# zero-hm-10-breakout.net
KiCad netlist of a schematic drawn in EAGLE
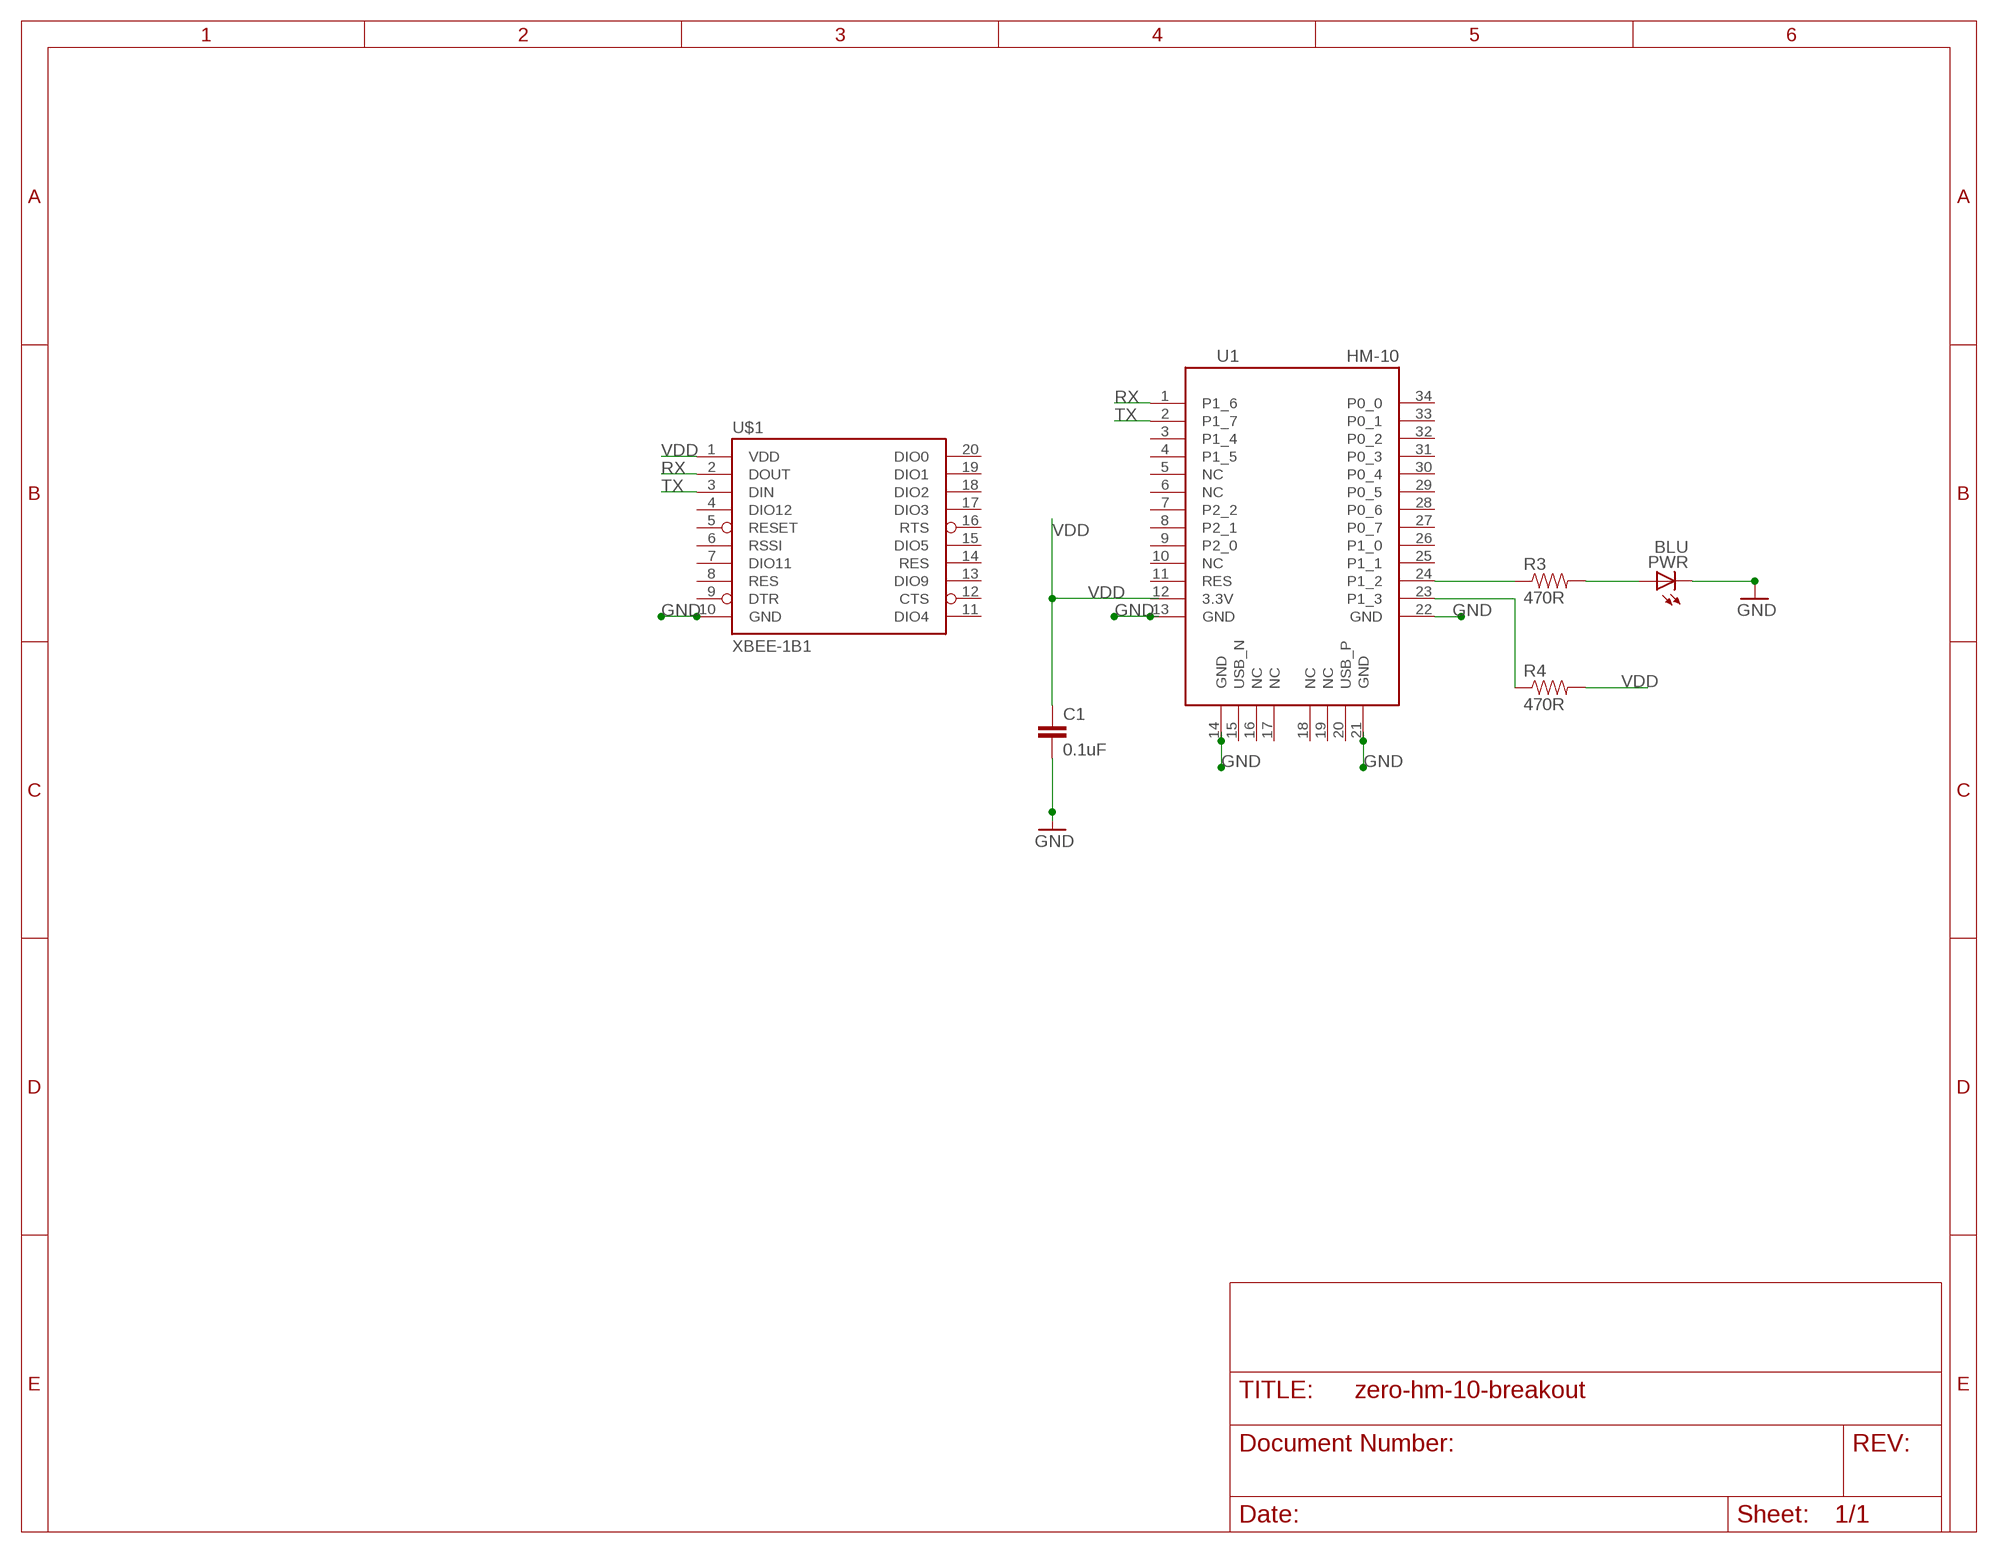
[diagram p0: schematic, sheet 1]

(export (version "E")
  (design (tool "Eeschema 10.0.6"))
  (components
    (comp (ref "C1")
      (value "0.1uF")
      (footprint "eagle-import:0603-CAP")
      (libsource (lib "eagle-import") (part "0.1UF-25V(+80/-20%)(0603)"))
    )
    (comp (ref "PWR")
      (value "BLU")
      (footprint "eagle-import:CHIPLED_0805")
      (libsource (lib "eagle-import") (part "LEDCHIPLED_0805"))
    )
    (comp (ref "R3")
      (value "470R")
      (footprint "eagle-import:0805")
      (libsource (lib "eagle-import") (part "0.3OHM-1/8W-1%(0805)"))
    )
    (comp (ref "R4")
      (value "470R")
      (footprint "eagle-import:0805")
      (libsource (lib "eagle-import") (part "0.3OHM-1/8W-1%(0805)"))
    )
    (comp (ref "U$1")
      (value "XBEE-1B1")
      (footprint "eagle-import:XBEE-1")
      (libsource (lib "eagle-import") (part "XBEE-1B1"))
    )
    (comp (ref "U1")
      (value "HM-10")
      (footprint "eagle-import:HM-10")
      (libsource (lib "eagle-import") (part "HM-10"))
    )
  )
  (nets
    (net (code "1") (name "/RX") (class "Default")
      (node (ref "U$1") (pin "2") (pinfunction "DOUT_2") (pintype "output"))
      (node (ref "U1") (pin "1") (pinfunction "P1_6_1") (pintype "bidirectional"))
    )
    (net (code "2") (name "/TX") (class "Default")
      (node (ref "U$1") (pin "3") (pinfunction "DIN_3") (pintype "input"))
      (node (ref "U1") (pin "2") (pinfunction "P1_7_2") (pintype "bidirectional"))
    )
    (net (code "3") (name "/VDD") (class "Default")
      (node (ref "C1") (pin "1") (pinfunction "1_1") (pintype "passive"))
      (node (ref "R4") (pin "2") (pinfunction "2_2") (pintype "passive"))
      (node (ref "U$1") (pin "1") (pinfunction "VDD_1") (pintype "power_in"))
      (node (ref "U1") (pin "12") (pinfunction "3.3V_12") (pintype "bidirectional"))
    )
    (net (code "4") (name "GND") (class "Default")
      (node (ref "C1") (pin "2") (pinfunction "2_2") (pintype "passive"))
      (node (ref "PWR") (pin "C") (pinfunction "C_C") (pintype "passive"))
      (node (ref "U$1") (pin "10") (pinfunction "GND_10") (pintype "power_in"))
      (node (ref "U1") (pin "13") (pinfunction "GND_13") (pintype "bidirectional"))
      (node (ref "U1") (pin "14") (pinfunction "GND_14") (pintype "bidirectional"))
      (node (ref "U1") (pin "21") (pinfunction "GND_21") (pintype "bidirectional"))
      (node (ref "U1") (pin "22") (pinfunction "GND_22") (pintype "bidirectional"))
    )
    (net (code "5") (name "Net-(PWR-PadA)") (class "Default")
      (node (ref "PWR") (pin "A") (pinfunction "A_A") (pintype "passive"))
      (node (ref "R3") (pin "2") (pinfunction "2_2") (pintype "passive"))
    )
    (net (code "6") (name "Net-(U1-P1_2)") (class "Default")
      (node (ref "R3") (pin "1") (pinfunction "1_1") (pintype "passive"))
      (node (ref "U1") (pin "24") (pinfunction "P1_2_24") (pintype "bidirectional"))
    )
    (net (code "7") (name "Net-(U1-P1_3)") (class "Default")
      (node (ref "R4") (pin "1") (pinfunction "1_1") (pintype "passive"))
      (node (ref "U1") (pin "23") (pinfunction "P1_3_23") (pintype "bidirectional"))
    )
    (net (code "8") (name "unconnected-(U$1-CTS-Pad12)") (class "Default")
      (node (ref "U$1") (pin "12") (pinfunction "CTS_12") (pintype "output"))
    )
    (net (code "9") (name "unconnected-(U$1-DIO0-Pad20)") (class "Default")
      (node (ref "U$1") (pin "20") (pinfunction "DIO0_20") (pintype "bidirectional"))
    )
    (net (code "10") (name "unconnected-(U$1-DIO1-Pad19)") (class "Default")
      (node (ref "U$1") (pin "19") (pinfunction "DIO1_19") (pintype "bidirectional"))
    )
    (net (code "11") (name "unconnected-(U$1-DIO2-Pad18)") (class "Default")
      (node (ref "U$1") (pin "18") (pinfunction "DIO2_18") (pintype "bidirectional"))
    )
    (net (code "12") (name "unconnected-(U$1-DIO3-Pad17)") (class "Default")
      (node (ref "U$1") (pin "17") (pinfunction "DIO3_17") (pintype "bidirectional"))
    )
    (net (code "13") (name "unconnected-(U$1-DIO4-Pad11)") (class "Default")
      (node (ref "U$1") (pin "11") (pinfunction "DIO4_11") (pintype "bidirectional"))
    )
    (net (code "14") (name "unconnected-(U$1-DIO5-Pad15)") (class "Default")
      (node (ref "U$1") (pin "15") (pinfunction "DIO5_15") (pintype "bidirectional"))
    )
    (net (code "15") (name "unconnected-(U$1-DIO9-Pad13)") (class "Default")
      (node (ref "U$1") (pin "13") (pinfunction "DIO9_13") (pintype "bidirectional"))
    )
    (net (code "16") (name "unconnected-(U$1-DIO11-Pad7)") (class "Default")
      (node (ref "U$1") (pin "7") (pinfunction "DIO11_7") (pintype "bidirectional"))
    )
    (net (code "17") (name "unconnected-(U$1-DIO12-Pad4)") (class "Default")
      (node (ref "U$1") (pin "4") (pinfunction "DIO12_4") (pintype "bidirectional"))
    )
    (net (code "18") (name "unconnected-(U$1-DTR-Pad9)") (class "Default")
      (node (ref "U$1") (pin "9") (pinfunction "DTR_9") (pintype "bidirectional"))
    )
    (net (code "19") (name "unconnected-(U$1-RES-Pad8)") (class "Default")
      (node (ref "U$1") (pin "8") (pinfunction "RES_8") (pintype "bidirectional"))
    )
    (net (code "20") (name "unconnected-(U$1-RES-Pad14)") (class "Default")
      (node (ref "U$1") (pin "14") (pinfunction "RES_14") (pintype "bidirectional"))
    )
    (net (code "21") (name "unconnected-(U$1-RESET-Pad5)") (class "Default")
      (node (ref "U$1") (pin "5") (pinfunction "RESET_5") (pintype "input"))
    )
    (net (code "22") (name "unconnected-(U$1-RSSI-Pad6)") (class "Default")
      (node (ref "U$1") (pin "6") (pinfunction "RSSI_6") (pintype "bidirectional"))
    )
    (net (code "23") (name "unconnected-(U$1-RTS-Pad16)") (class "Default")
      (node (ref "U$1") (pin "16") (pinfunction "RTS_16") (pintype "input"))
    )
    (net (code "24") (name "unconnected-(U1-NC-Pad5)") (class "Default")
      (node (ref "U1") (pin "5") (pinfunction "NC_5") (pintype "bidirectional"))
    )
    (net (code "25") (name "unconnected-(U1-NC-Pad6)") (class "Default")
      (node (ref "U1") (pin "6") (pinfunction "NC_6") (pintype "bidirectional"))
    )
    (net (code "26") (name "unconnected-(U1-NC-Pad10)") (class "Default")
      (node (ref "U1") (pin "10") (pinfunction "NC_10") (pintype "bidirectional"))
    )
    (net (code "27") (name "unconnected-(U1-NC-Pad16)") (class "Default")
      (node (ref "U1") (pin "16") (pinfunction "NC_16") (pintype "bidirectional"))
    )
    (net (code "28") (name "unconnected-(U1-NC-Pad17)") (class "Default")
      (node (ref "U1") (pin "17") (pinfunction "NC_17") (pintype "bidirectional"))
    )
    (net (code "29") (name "unconnected-(U1-NC-Pad18)") (class "Default")
      (node (ref "U1") (pin "18") (pinfunction "NC_18") (pintype "bidirectional"))
    )
    (net (code "30") (name "unconnected-(U1-NC-Pad19)") (class "Default")
      (node (ref "U1") (pin "19") (pinfunction "NC_19") (pintype "bidirectional"))
    )
    (net (code "31") (name "unconnected-(U1-P0_0-Pad34)") (class "Default")
      (node (ref "U1") (pin "34") (pinfunction "P0_0_34") (pintype "bidirectional"))
    )
    (net (code "32") (name "unconnected-(U1-P0_1-Pad33)") (class "Default")
      (node (ref "U1") (pin "33") (pinfunction "P0_1_33") (pintype "bidirectional"))
    )
    (net (code "33") (name "unconnected-(U1-P0_2-Pad32)") (class "Default")
      (node (ref "U1") (pin "32") (pinfunction "P0_2_32") (pintype "bidirectional"))
    )
    (net (code "34") (name "unconnected-(U1-P0_3-Pad31)") (class "Default")
      (node (ref "U1") (pin "31") (pinfunction "P0_3_31") (pintype "bidirectional"))
    )
    (net (code "35") (name "unconnected-(U1-P0_4-Pad30)") (class "Default")
      (node (ref "U1") (pin "30") (pinfunction "P0_4_30") (pintype "bidirectional"))
    )
    (net (code "36") (name "unconnected-(U1-P0_5-Pad29)") (class "Default")
      (node (ref "U1") (pin "29") (pinfunction "P0_5_29") (pintype "bidirectional"))
    )
    (net (code "37") (name "unconnected-(U1-P0_6-Pad28)") (class "Default")
      (node (ref "U1") (pin "28") (pinfunction "P0_6_28") (pintype "bidirectional"))
    )
    (net (code "38") (name "unconnected-(U1-P0_7-Pad27)") (class "Default")
      (node (ref "U1") (pin "27") (pinfunction "P0_7_27") (pintype "bidirectional"))
    )
    (net (code "39") (name "unconnected-(U1-P1_0-Pad26)") (class "Default")
      (node (ref "U1") (pin "26") (pinfunction "P1_0_26") (pintype "bidirectional"))
    )
    (net (code "40") (name "unconnected-(U1-P1_1-Pad25)") (class "Default")
      (node (ref "U1") (pin "25") (pinfunction "P1_1_25") (pintype "bidirectional"))
    )
    (net (code "41") (name "unconnected-(U1-P1_4-Pad3)") (class "Default")
      (node (ref "U1") (pin "3") (pinfunction "P1_4_3") (pintype "bidirectional"))
    )
    (net (code "42") (name "unconnected-(U1-P1_5-Pad4)") (class "Default")
      (node (ref "U1") (pin "4") (pinfunction "P1_5_4") (pintype "bidirectional"))
    )
    (net (code "43") (name "unconnected-(U1-P2_0-Pad9)") (class "Default")
      (node (ref "U1") (pin "9") (pinfunction "P2_0_9") (pintype "bidirectional"))
    )
    (net (code "44") (name "unconnected-(U1-P2_1-Pad8)") (class "Default")
      (node (ref "U1") (pin "8") (pinfunction "P2_1_8") (pintype "bidirectional"))
    )
    (net (code "45") (name "unconnected-(U1-P2_2-Pad7)") (class "Default")
      (node (ref "U1") (pin "7") (pinfunction "P2_2_7") (pintype "bidirectional"))
    )
    (net (code "46") (name "unconnected-(U1-RES-Pad11)") (class "Default")
      (node (ref "U1") (pin "11") (pinfunction "RES_11") (pintype "bidirectional"))
    )
    (net (code "47") (name "unconnected-(U1-USB_N-Pad15)") (class "Default")
      (node (ref "U1") (pin "15") (pinfunction "USB_N_15") (pintype "bidirectional"))
    )
    (net (code "48") (name "unconnected-(U1-USB_P-Pad20)") (class "Default")
      (node (ref "U1") (pin "20") (pinfunction "USB_P_20") (pintype "bidirectional"))
    )
  )
)
